# STM32.net
KiCad netlist of a schematic drawn in Altium Designer
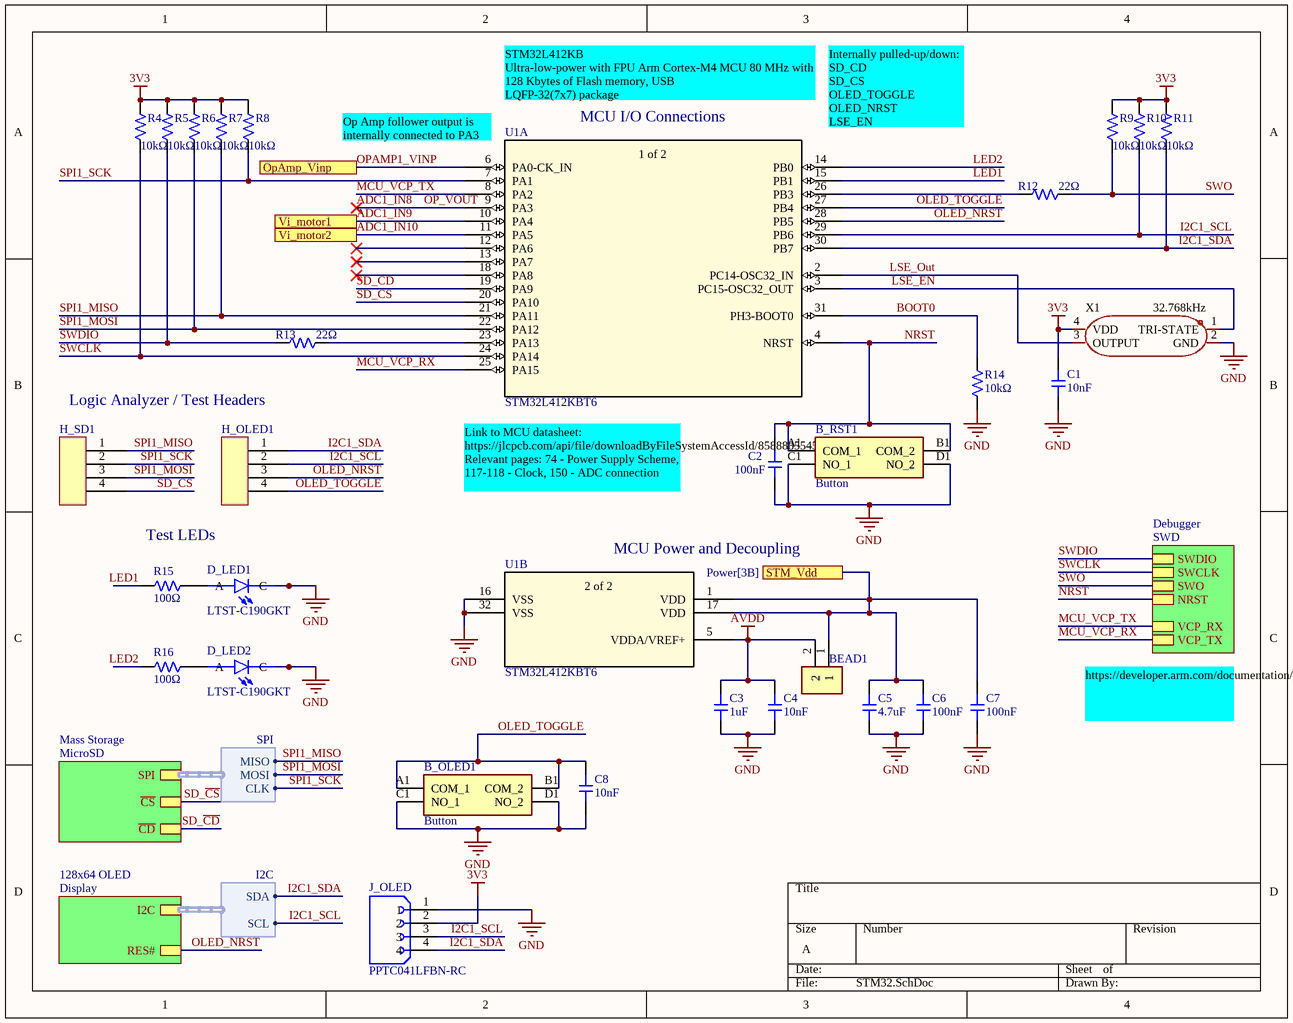
[diagram p0: STM32.SchDoc]

(export (version "E")
  (design (tool "Eeschema 10.0.6"))
  (components
    (comp (ref "BEAD1")
      (value "GZ1608D601TF")
      (footprint "SamacSys:BEADC1608X95N")
      (description "Ferrite Bead")
      (libsource (lib "SamacSys") (part "GZ1608D601TF"))
    )
    (comp (ref "B_OLED1")
      (value "Button")
      (footprint "SamacSys:TS1187ABAB")
      (fields (field (name "MANUFACTURER_PART_NUMBER") "TS-1187A-B-A-B"))
      (libsource (lib "SamacSys") (part "TS-1187A-B-A-B"))
    )
    (comp (ref "B_RST1")
      (value "Button")
      (footprint "SamacSys:TS1187ABAB")
      (fields (field (name "MANUFACTURER_PART_NUMBER") "TS-1187A-B-A-B"))
      (libsource (lib "SamacSys") (part "TS-1187A-B-A-B"))
    )
    (comp (ref "C1")
      (value "CL05B103KB5NNNC")
      (footprint "CAP-0402")
      (description "Capacitor, Ceramic (MLCC), 10nF, ±10%, 50V, X7R, ±10%, SMD 0402")
      (fields
        (field (name "JLCPCB BASIC PART") "Yes")
        (field (name "CAPACITANCE") "10nF")
        (field (name "JLCPCB PART NUMBER") "C15195")
      )
      (libsource (lib "jlcpcb_2024_10_capacitors_basic") (part "CL05B103KB5NNNC"))
    )
    (comp (ref "C2")
      (value "CL05B104KB54PNC")
      (footprint "CAP-0402")
      (description "Capacitor, Ceramic (MLCC), 100nF, ±10%, 50V, X7R, ±10%, SMD 0402")
      (fields
        (field (name "JLCPCB BASIC PART") "Yes")
        (field (name "CAPACITANCE") "100nF")
        (field (name "JLCPCB PART NUMBER") "C307331")
      )
      (libsource (lib "jlcpcb_2024_10_capacitors_basic") (part "CL05B104KB54PNC"))
    )
    (comp (ref "C3")
      (value "CL05A105KA5NQNC")
      (footprint "CAP-0402")
      (description "Capacitor, Ceramic (MLCC), 1uF, ±10%, 25V, X5R, ±10%, SMD 0402")
      (fields
        (field (name "JLCPCB BASIC PART") "Yes")
        (field (name "CAPACITANCE") "1uF")
        (field (name "JLCPCB PART NUMBER") "C52923")
      )
      (libsource (lib "jlcpcb_2024_10_capacitors_basic") (part "CL05A105KA5NQNC"))
    )
    (comp (ref "C4")
      (value "CL05B103KB5NNNC")
      (footprint "CAP-0402")
      (description "Capacitor, Ceramic (MLCC), 10nF, ±10%, 50V, X7R, ±10%, SMD 0402")
      (fields
        (field (name "JLCPCB BASIC PART") "Yes")
        (field (name "CAPACITANCE") "10nF")
        (field (name "JLCPCB PART NUMBER") "C15195")
      )
      (libsource (lib "jlcpcb_2024_10_capacitors_basic") (part "CL05B103KB5NNNC"))
    )
    (comp (ref "C5")
      (value "CL05A475MP5NRNC")
      (footprint "CAP-0402")
      (description "Capacitor, Ceramic (MLCC), 4.7uF, ±20%, 10V, X5R, ±20%, SMD 0402")
      (fields
        (field (name "JLCPCB BASIC PART") "Yes")
        (field (name "CAPACITANCE") "4.7uF")
        (field (name "JLCPCB PART NUMBER") "C23733")
      )
      (libsource (lib "jlcpcb_2024_10_capacitors_basic") (part "CL05A475MP5NRNC"))
    )
    (comp (ref "C6")
      (value "CL05B104KO5NNNC")
      (footprint "CAP-0402")
      (description "Capacitor, Ceramic (MLCC), 100nF, ±10%, 16V, X7R, ±10%, SMD 0402")
      (fields
        (field (name "JLCPCB BASIC PART") "Yes")
        (field (name "CAPACITANCE") "100nF")
        (field (name "JLCPCB PART NUMBER") "C1525")
      )
      (libsource (lib "jlcpcb_2024_10_capacitors_basic") (part "CL05B104KO5NNNC"))
    )
    (comp (ref "C7")
      (value "CL05B104KO5NNNC")
      (footprint "CAP-0402")
      (description "Capacitor, Ceramic (MLCC), 100nF, ±10%, 16V, X7R, ±10%, SMD 0402")
      (fields
        (field (name "JLCPCB BASIC PART") "Yes")
        (field (name "CAPACITANCE") "100nF")
        (field (name "JLCPCB PART NUMBER") "C1525")
      )
      (libsource (lib "jlcpcb_2024_10_capacitors_basic") (part "CL05B104KO5NNNC"))
    )
    (comp (ref "C8")
      (value "CL05B103KB5NNNC")
      (footprint "CAP-0402")
      (description "Capacitor, Ceramic (MLCC), 10nF, ±10%, 50V, X7R, ±10%, SMD 0402")
      (fields
        (field (name "JLCPCB BASIC PART") "Yes")
        (field (name "CAPACITANCE") "10nF")
        (field (name "JLCPCB PART NUMBER") "C15195")
      )
      (libsource (lib "jlcpcb_2024_10_capacitors_basic") (part "CL05B103KB5NNNC"))
    )
    (comp (ref "D_LED1")
      (value "LTST-C190GKT")
      (footprint "LEDM1608X80")
      (fields (field (name "MF") "{'manufacturer': u'Lite-On Inc.'}"))
      (libsource (lib "LTST-C190GKT") (part "LTST-C190GKT"))
    )
    (comp (ref "D_LED2")
      (value "LTST-C190GKT")
      (footprint "LEDM1608X80")
      (fields (field (name "MF") "{'manufacturer': u'Lite-On Inc.'}"))
      (libsource (lib "LTST-C190GKT") (part "LTST-C190GKT"))
    )
    (comp (ref "H_OLED1")
      (value "4-pin Header")
      (footprint "4-pin Header")
      (description "4-pin Header 0.1mm pitch")
      (libsource (lib "Schlib1") (part "4-pin Header"))
    )
    (comp (ref "H_SD1")
      (value "4-pin Header")
      (footprint "4-pin Header")
      (description "4-pin Header 0.1mm pitch")
      (libsource (lib "Schlib1") (part "4-pin Header"))
    )
    (comp (ref "J_OLED")
      (value "PPTC041LFBN-RC")
      (footprint "SULLINS_PPTC041LFBN-RC")
      (description "4 Position Header Connector 0.100 (2.54mm) Through Hole Tin")
      (fields (field (name "MF") "Sullins Connector"))
      (libsource (lib "PPTC041LFBN-RC") (part "PPTC041LFBN-RC"))
    )
    (comp (ref "R4")
      (value "0402WGF1002TCE")
      (footprint "RES-0402")
      (description "Resistor, 10kΩ, ±1%, 62.5mW, 50V, ±100ppm/℃, -55℃~+155℃, SMD 0402")
      (fields
        (field (name "MANUFACTURER") "Uniroyal")
        (field (name "JLCPCB PART NUMBER") "C25744")
        (field (name "RESISTANCE") "10kΩ")
      )
      (libsource (lib "jlcpcb_2024_10_resistors_basic") (part "0402WGF1002TCE"))
    )
    (comp (ref "R5")
      (value "0402WGF1002TCE")
      (footprint "RES-0402")
      (description "Resistor, 10kΩ, ±1%, 62.5mW, 50V, ±100ppm/℃, -55℃~+155℃, SMD 0402")
      (fields
        (field (name "MANUFACTURER") "Uniroyal")
        (field (name "JLCPCB PART NUMBER") "C25744")
        (field (name "RESISTANCE") "10kΩ")
      )
      (libsource (lib "jlcpcb_2024_10_resistors_basic") (part "0402WGF1002TCE"))
    )
    (comp (ref "R6")
      (value "0402WGF1002TCE")
      (footprint "RES-0402")
      (description "Resistor, 10kΩ, ±1%, 62.5mW, 50V, ±100ppm/℃, -55℃~+155℃, SMD 0402")
      (fields
        (field (name "MANUFACTURER") "Uniroyal")
        (field (name "JLCPCB PART NUMBER") "C25744")
        (field (name "RESISTANCE") "10kΩ")
      )
      (libsource (lib "jlcpcb_2024_10_resistors_basic") (part "0402WGF1002TCE"))
    )
    (comp (ref "R7")
      (value "0402WGF1002TCE")
      (footprint "RES-0402")
      (description "Resistor, 10kΩ, ±1%, 62.5mW, 50V, ±100ppm/℃, -55℃~+155℃, SMD 0402")
      (fields
        (field (name "MANUFACTURER") "Uniroyal")
        (field (name "JLCPCB PART NUMBER") "C25744")
        (field (name "RESISTANCE") "10kΩ")
      )
      (libsource (lib "jlcpcb_2024_10_resistors_basic") (part "0402WGF1002TCE"))
    )
    (comp (ref "R8")
      (value "0402WGF1002TCE")
      (footprint "RES-0402")
      (description "Resistor, 10kΩ, ±1%, 62.5mW, 50V, ±100ppm/℃, -55℃~+155℃, SMD 0402")
      (fields
        (field (name "MANUFACTURER") "Uniroyal")
        (field (name "JLCPCB PART NUMBER") "C25744")
        (field (name "RESISTANCE") "10kΩ")
      )
      (libsource (lib "jlcpcb_2024_10_resistors_basic") (part "0402WGF1002TCE"))
    )
    (comp (ref "R9")
      (value "0402WGF1002TCE")
      (footprint "RES-0402")
      (description "Resistor, 10kΩ, ±1%, 62.5mW, 50V, ±100ppm/℃, -55℃~+155℃, SMD 0402")
      (fields
        (field (name "MANUFACTURER") "Uniroyal")
        (field (name "JLCPCB PART NUMBER") "C25744")
        (field (name "RESISTANCE") "10kΩ")
      )
      (libsource (lib "jlcpcb_2024_10_resistors_basic") (part "0402WGF1002TCE"))
    )
    (comp (ref "R10")
      (value "0402WGF1002TCE")
      (footprint "RES-0402")
      (description "Resistor, 10kΩ, ±1%, 62.5mW, 50V, ±100ppm/℃, -55℃~+155℃, SMD 0402")
      (fields
        (field (name "MANUFACTURER") "Uniroyal")
        (field (name "JLCPCB PART NUMBER") "C25744")
        (field (name "RESISTANCE") "10kΩ")
      )
      (libsource (lib "jlcpcb_2024_10_resistors_basic") (part "0402WGF1002TCE"))
    )
    (comp (ref "R11")
      (value "0402WGF1002TCE")
      (footprint "RES-0402")
      (description "Resistor, 10kΩ, ±1%, 62.5mW, 50V, ±100ppm/℃, -55℃~+155℃, SMD 0402")
      (fields
        (field (name "MANUFACTURER") "Uniroyal")
        (field (name "JLCPCB PART NUMBER") "C25744")
        (field (name "RESISTANCE") "10kΩ")
      )
      (libsource (lib "jlcpcb_2024_10_resistors_basic") (part "0402WGF1002TCE"))
    )
    (comp (ref "R12")
      (value "0402WGF220JTCE")
      (footprint "RES-0402")
      (description "Resistor, 22Ω, ±1%, 62.5mW, 50V, ±200ppm/℃, -55℃~+155℃, SMD 0402")
      (fields
        (field (name "MANUFACTURER") "Uniroyal")
        (field (name "JLCPCB PART NUMBER") "C25092")
        (field (name "RESISTANCE") "22Ω")
      )
      (libsource (lib "jlcpcb_2024_10_resistors_basic") (part "0402WGF220JTCE"))
    )
    (comp (ref "R13")
      (value "0402WGF220JTCE")
      (footprint "RES-0402")
      (description "Resistor, 22Ω, ±1%, 62.5mW, 50V, ±200ppm/℃, -55℃~+155℃, SMD 0402")
      (fields
        (field (name "MANUFACTURER") "Uniroyal")
        (field (name "JLCPCB PART NUMBER") "C25092")
        (field (name "RESISTANCE") "22Ω")
      )
      (libsource (lib "jlcpcb_2024_10_resistors_basic") (part "0402WGF220JTCE"))
    )
    (comp (ref "R14")
      (value "0402WGF1002TCE")
      (footprint "RES-0402")
      (description "Resistor, 10kΩ, ±1%, 62.5mW, 50V, ±100ppm/℃, -55℃~+155℃, SMD 0402")
      (fields
        (field (name "MANUFACTURER") "Uniroyal")
        (field (name "JLCPCB PART NUMBER") "C25744")
        (field (name "RESISTANCE") "10kΩ")
      )
      (libsource (lib "jlcpcb_2024_10_resistors_basic") (part "0402WGF1002TCE"))
    )
    (comp (ref "R15")
      (value "0402WGF1000TCE")
      (footprint "RES-0402")
      (description "Resistor, 100Ω, ±1%, 62.5mW, 50V, ±200ppm/℃, -55℃~+155℃, SMD 0402")
      (fields
        (field (name "MANUFACTURER") "Uniroyal")
        (field (name "JLCPCB PART NUMBER") "C25076")
        (field (name "RESISTANCE") "100Ω")
      )
      (libsource (lib "jlcpcb_2024_10_resistors_basic") (part "0402WGF1000TCE"))
    )
    (comp (ref "R16")
      (value "0402WGF1000TCE")
      (footprint "RES-0402")
      (description "Resistor, 100Ω, ±1%, 62.5mW, 50V, ±200ppm/℃, -55℃~+155℃, SMD 0402")
      (fields
        (field (name "MANUFACTURER") "Uniroyal")
        (field (name "JLCPCB PART NUMBER") "C25076")
        (field (name "RESISTANCE") "100Ω")
      )
      (libsource (lib "jlcpcb_2024_10_resistors_basic") (part "0402WGF1000TCE"))
    )
    (comp (ref "U1")
      (value "STM32L412KBT6")
      (footprint "LQFP-32")
      (description "No Description Available")
      (libsource (lib "STM32L412KBT6") (part "STM32L412KBT6"))
    )
    (comp (ref "X1")
      (value "32.768kHz")
      (footprint "OSC-SMD_4P-L3.2-W2.5-BL:OSC-SMD_4P-L3.2-W2.5-BL")
      (fields
        (field (name "MANUFACTURER") "SCTF(星通时频)")
        (field (name "MANUFACTURER PART") "SX3M32.768KM20F30TNN")
      )
      (libsource (lib "SX3M32.768KM20F30TNN1_SX3M32.768KM20F30TNN") (part "SX3M32.768KM20F30TNN"))
    )
  )
  (nets
    (net (code "4") (name "/ADC1_IN8") (class "Default")
      (node (ref "U1") (pin "9") (pinfunction "PA3_9") (pintype "bidirectional+no_connect"))
    )
    (net (code "5") (name "/ADC1_IN9") (class "Default")
      (node (ref "U1") (pin "10") (pinfunction "PA4_10") (pintype "bidirectional"))
    )
    (net (code "6") (name "/ADC1_IN10") (class "Default")
      (node (ref "U1") (pin "11") (pinfunction "PA5_11") (pintype "bidirectional"))
    )
    (net (code "7") (name "/BOOT0") (class "Default")
      (node (ref "R14") (pin "2") (pinfunction "2_2") (pintype "passive"))
      (node (ref "U1") (pin "31") (pinfunction "PH3-BOOT0_31") (pintype "bidirectional"))
    )
    (net (code "8") (name "/I2C1_SCL") (class "Default")
      (node (ref "H_OLED1") (pin "2") (pinfunction "2_2") (pintype "passive"))
      (node (ref "J_OLED") (pin "3") (pinfunction "3_3") (pintype "passive"))
      (node (ref "R10") (pin "1") (pinfunction "1_1") (pintype "passive"))
      (node (ref "U1") (pin "29") (pinfunction "PB6_29") (pintype "bidirectional"))
    )
    (net (code "9") (name "/I2C1_SDA") (class "Default")
      (node (ref "H_OLED1") (pin "1") (pinfunction "1_1") (pintype "passive"))
      (node (ref "J_OLED") (pin "4") (pinfunction "4_4") (pintype "passive"))
      (node (ref "R11") (pin "1") (pinfunction "1_1") (pintype "passive"))
      (node (ref "U1") (pin "30") (pinfunction "PB7_30") (pintype "bidirectional"))
    )
    (net (code "10") (name "/LED1") (class "Default")
      (node (ref "R15") (pin "1") (pinfunction "1_1") (pintype "passive"))
      (node (ref "U1") (pin "15") (pinfunction "PB1_15") (pintype "bidirectional"))
    )
    (net (code "11") (name "/LED2") (class "Default")
      (node (ref "R16") (pin "1") (pinfunction "1_1") (pintype "passive"))
      (node (ref "U1") (pin "14") (pinfunction "PB0_14") (pintype "bidirectional"))
    )
    (net (code "12") (name "/LSE_EN") (class "Default")
      (node (ref "U1") (pin "3") (pinfunction "PC15-OSC32_OUT_3") (pintype "bidirectional"))
      (node (ref "X1") (pin "1") (pinfunction "TRI-STATE_1") (pintype "passive"))
    )
    (net (code "13") (name "/LSE_Out") (class "Default")
      (node (ref "U1") (pin "2") (pinfunction "PC14-OSC32_IN_2") (pintype "bidirectional"))
      (node (ref "X1") (pin "3") (pinfunction "OUTPUT_3") (pintype "passive"))
    )
    (net (code "14") (name "/MCU_VCP_RX") (class "Default")
      (node (ref "U1") (pin "25") (pinfunction "PA15_25") (pintype "bidirectional"))
    )
    (net (code "15") (name "/MCU_VCP_TX") (class "Default")
      (node (ref "U1") (pin "8") (pinfunction "PA2_8") (pintype "bidirectional"))
    )
    (net (code "16") (name "/NRST") (class "Default")
      (node (ref "B_RST1") (pin "A1") (pinfunction "COM_1_A1") (pintype "passive"))
      (node (ref "B_RST1") (pin "B1") (pinfunction "COM_2_B1") (pintype "passive"))
      (node (ref "C2") (pin "2") (pinfunction "2_2") (pintype "passive"))
      (node (ref "U1") (pin "4") (pinfunction "NRST_4") (pintype "bidirectional"))
    )
    (net (code "17") (name "/OLED_NRST") (class "Default")
      (node (ref "H_OLED1") (pin "3") (pinfunction "3_3") (pintype "passive"))
      (node (ref "U1") (pin "28") (pinfunction "PB5_28") (pintype "bidirectional"))
    )
    (net (code "18") (name "/OLED_TOGGLE") (class "Default")
      (node (ref "B_OLED1") (pin "A1") (pinfunction "COM_1_A1") (pintype "passive"))
      (node (ref "B_OLED1") (pin "B1") (pinfunction "COM_2_B1") (pintype "passive"))
      (node (ref "C8") (pin "2") (pinfunction "2_2") (pintype "passive"))
      (node (ref "H_OLED1") (pin "4") (pinfunction "4_4") (pintype "passive"))
      (node (ref "U1") (pin "27") (pinfunction "PB4_27") (pintype "bidirectional"))
    )
    (net (code "19") (name "/OPAMP1_VINP") (class "Default")
      (node (ref "U1") (pin "6") (pinfunction "PA0-CK_IN_6") (pintype "bidirectional"))
    )
    (net (code "20") (name "/SD_~{CD}") (class "Default")
      (node (ref "U1") (pin "19") (pinfunction "PA9_19") (pintype "bidirectional"))
    )
    (net (code "21") (name "/SD_~{CS}") (class "Default")
      (node (ref "H_SD1") (pin "4") (pinfunction "4_4") (pintype "passive"))
      (node (ref "U1") (pin "20") (pinfunction "PA10_20") (pintype "bidirectional"))
    )
    (net (code "22") (name "/SPI1_MISO") (class "Default")
      (node (ref "H_SD1") (pin "1") (pinfunction "1_1") (pintype "passive"))
      (node (ref "R7") (pin "1") (pinfunction "1_1") (pintype "passive"))
      (node (ref "U1") (pin "21") (pinfunction "PA11_21") (pintype "bidirectional"))
    )
    (net (code "23") (name "/SPI1_MOSI") (class "Default")
      (node (ref "H_SD1") (pin "3") (pinfunction "3_3") (pintype "passive"))
      (node (ref "R6") (pin "1") (pinfunction "1_1") (pintype "passive"))
      (node (ref "U1") (pin "22") (pinfunction "PA12_22") (pintype "bidirectional"))
    )
    (net (code "24") (name "/SPI1_SCK") (class "Default")
      (node (ref "H_SD1") (pin "2") (pinfunction "2_2") (pintype "passive"))
      (node (ref "R8") (pin "1") (pinfunction "1_1") (pintype "passive"))
      (node (ref "U1") (pin "7") (pinfunction "PA1_7") (pintype "bidirectional"))
    )
    (net (code "25") (name "/STM_Vdd") (class "Default")
      (node (ref "BEAD1") (pin "1") (pinfunction "1_1") (pintype "passive"))
      (node (ref "C5") (pin "2") (pinfunction "2_2") (pintype "passive"))
      (node (ref "C6") (pin "2") (pinfunction "2_2") (pintype "passive"))
      (node (ref "C7") (pin "2") (pinfunction "2_2") (pintype "passive"))
      (node (ref "U1") (pin "1") (pinfunction "VDD_1") (pintype "power_in"))
      (node (ref "U1") (pin "17") (pinfunction "VDD_17") (pintype "power_in"))
    )
    (net (code "26") (name "/SWCLK") (class "Default")
      (node (ref "R4") (pin "1") (pinfunction "1_1") (pintype "passive"))
      (node (ref "U1") (pin "24") (pinfunction "PA14_24") (pintype "bidirectional"))
    )
    (net (code "27") (name "/SWDIO") (class "Default")
      (node (ref "R13") (pin "1") (pinfunction "1_1") (pintype "passive"))
      (node (ref "R5") (pin "1") (pinfunction "1_1") (pintype "passive"))
    )
    (net (code "28") (name "/SWO") (class "Default")
      (node (ref "R12") (pin "2") (pinfunction "2_2") (pintype "passive"))
      (node (ref "R9") (pin "1") (pinfunction "1_1") (pintype "passive"))
    )
    (net (code "31") (name "3V3") (class "Default")
      (node (ref "C1") (pin "2") (pinfunction "2_2") (pintype "passive"))
      (node (ref "J_OLED") (pin "2") (pinfunction "2_2") (pintype "passive"))
      (node (ref "R10") (pin "2") (pinfunction "2_2") (pintype "passive"))
      (node (ref "R11") (pin "2") (pinfunction "2_2") (pintype "passive"))
      (node (ref "R4") (pin "2") (pinfunction "2_2") (pintype "passive"))
      (node (ref "R5") (pin "2") (pinfunction "2_2") (pintype "passive"))
      (node (ref "R6") (pin "2") (pinfunction "2_2") (pintype "passive"))
      (node (ref "R7") (pin "2") (pinfunction "2_2") (pintype "passive"))
      (node (ref "R8") (pin "2") (pinfunction "2_2") (pintype "passive"))
      (node (ref "R9") (pin "2") (pinfunction "2_2") (pintype "passive"))
      (node (ref "X1") (pin "4") (pinfunction "VDD_4") (pintype "passive"))
    )
    (net (code "32") (name "AVDD") (class "Default")
      (node (ref "BEAD1") (pin "2") (pinfunction "2_2") (pintype "passive"))
      (node (ref "C3") (pin "2") (pinfunction "2_2") (pintype "passive"))
      (node (ref "C4") (pin "2") (pinfunction "2_2") (pintype "passive"))
      (node (ref "U1") (pin "5") (pinfunction "VDDA/VREF+_5") (pintype "power_in"))
    )
    (net (code "33") (name "GND") (class "Default")
      (node (ref "B_OLED1") (pin "C1") (pinfunction "NO_1_C1") (pintype "passive"))
      (node (ref "B_OLED1") (pin "D1") (pinfunction "NO_2_D1") (pintype "passive"))
      (node (ref "B_RST1") (pin "C1") (pinfunction "NO_1_C1") (pintype "passive"))
      (node (ref "B_RST1") (pin "D1") (pinfunction "NO_2_D1") (pintype "passive"))
      (node (ref "C1") (pin "1") (pinfunction "1_1") (pintype "passive"))
      (node (ref "C2") (pin "1") (pinfunction "1_1") (pintype "passive"))
      (node (ref "C3") (pin "1") (pinfunction "1_1") (pintype "passive"))
      (node (ref "C4") (pin "1") (pinfunction "1_1") (pintype "passive"))
      (node (ref "C5") (pin "1") (pinfunction "1_1") (pintype "passive"))
      (node (ref "C6") (pin "1") (pinfunction "1_1") (pintype "passive"))
      (node (ref "C7") (pin "1") (pinfunction "1_1") (pintype "passive"))
      (node (ref "C8") (pin "1") (pinfunction "1_1") (pintype "passive"))
      (node (ref "D_LED1") (pin "C") (pinfunction "C_C") (pintype "passive"))
      (node (ref "D_LED2") (pin "C") (pinfunction "C_C") (pintype "passive"))
      (node (ref "J_OLED") (pin "1") (pinfunction "1_1") (pintype "passive"))
      (node (ref "R14") (pin "1") (pinfunction "1_1") (pintype "passive"))
      (node (ref "U1") (pin "16") (pinfunction "VSS_16") (pintype "power_in"))
      (node (ref "U1") (pin "32") (pinfunction "VSS_32") (pintype "power_in"))
      (node (ref "X1") (pin "2") (pinfunction "GND_2") (pintype "passive"))
    )
    (net (code "34") (name "Net-(D_LED1-PadA)") (class "Default")
      (node (ref "D_LED1") (pin "A") (pinfunction "A_A") (pintype "passive"))
      (node (ref "R15") (pin "2") (pinfunction "2_2") (pintype "passive"))
    )
    (net (code "35") (name "Net-(D_LED2-PadA)") (class "Default")
      (node (ref "D_LED2") (pin "A") (pinfunction "A_A") (pintype "passive"))
      (node (ref "R16") (pin "2") (pinfunction "2_2") (pintype "passive"))
    )
    (net (code "36") (name "Net-(U1A-PA13)") (class "Default")
      (node (ref "R13") (pin "2") (pinfunction "2_2") (pintype "passive"))
      (node (ref "U1") (pin "23") (pinfunction "PA13_23") (pintype "bidirectional"))
    )
    (net (code "37") (name "Net-(U1A-PB3)") (class "Default")
      (node (ref "R12") (pin "1") (pinfunction "1_1") (pintype "passive"))
      (node (ref "U1") (pin "26") (pinfunction "PB3_26") (pintype "bidirectional"))
    )
    (net (code "38") (name "unconnected-(U1A-PA6-Pad12)") (class "Default")
      (node (ref "U1") (pin "12") (pinfunction "PA6_12") (pintype "bidirectional+no_connect"))
    )
    (net (code "39") (name "unconnected-(U1A-PA7-Pad13)") (class "Default")
      (node (ref "U1") (pin "13") (pinfunction "PA7_13") (pintype "bidirectional+no_connect"))
    )
    (net (code "40") (name "unconnected-(U1A-PA8-Pad18)") (class "Default")
      (node (ref "U1") (pin "18") (pinfunction "PA8_18") (pintype "bidirectional+no_connect"))
    )
  )
)
